# bh_netlan_0_alph.net
KiCad netlist of a schematic drawn in Altium Designer
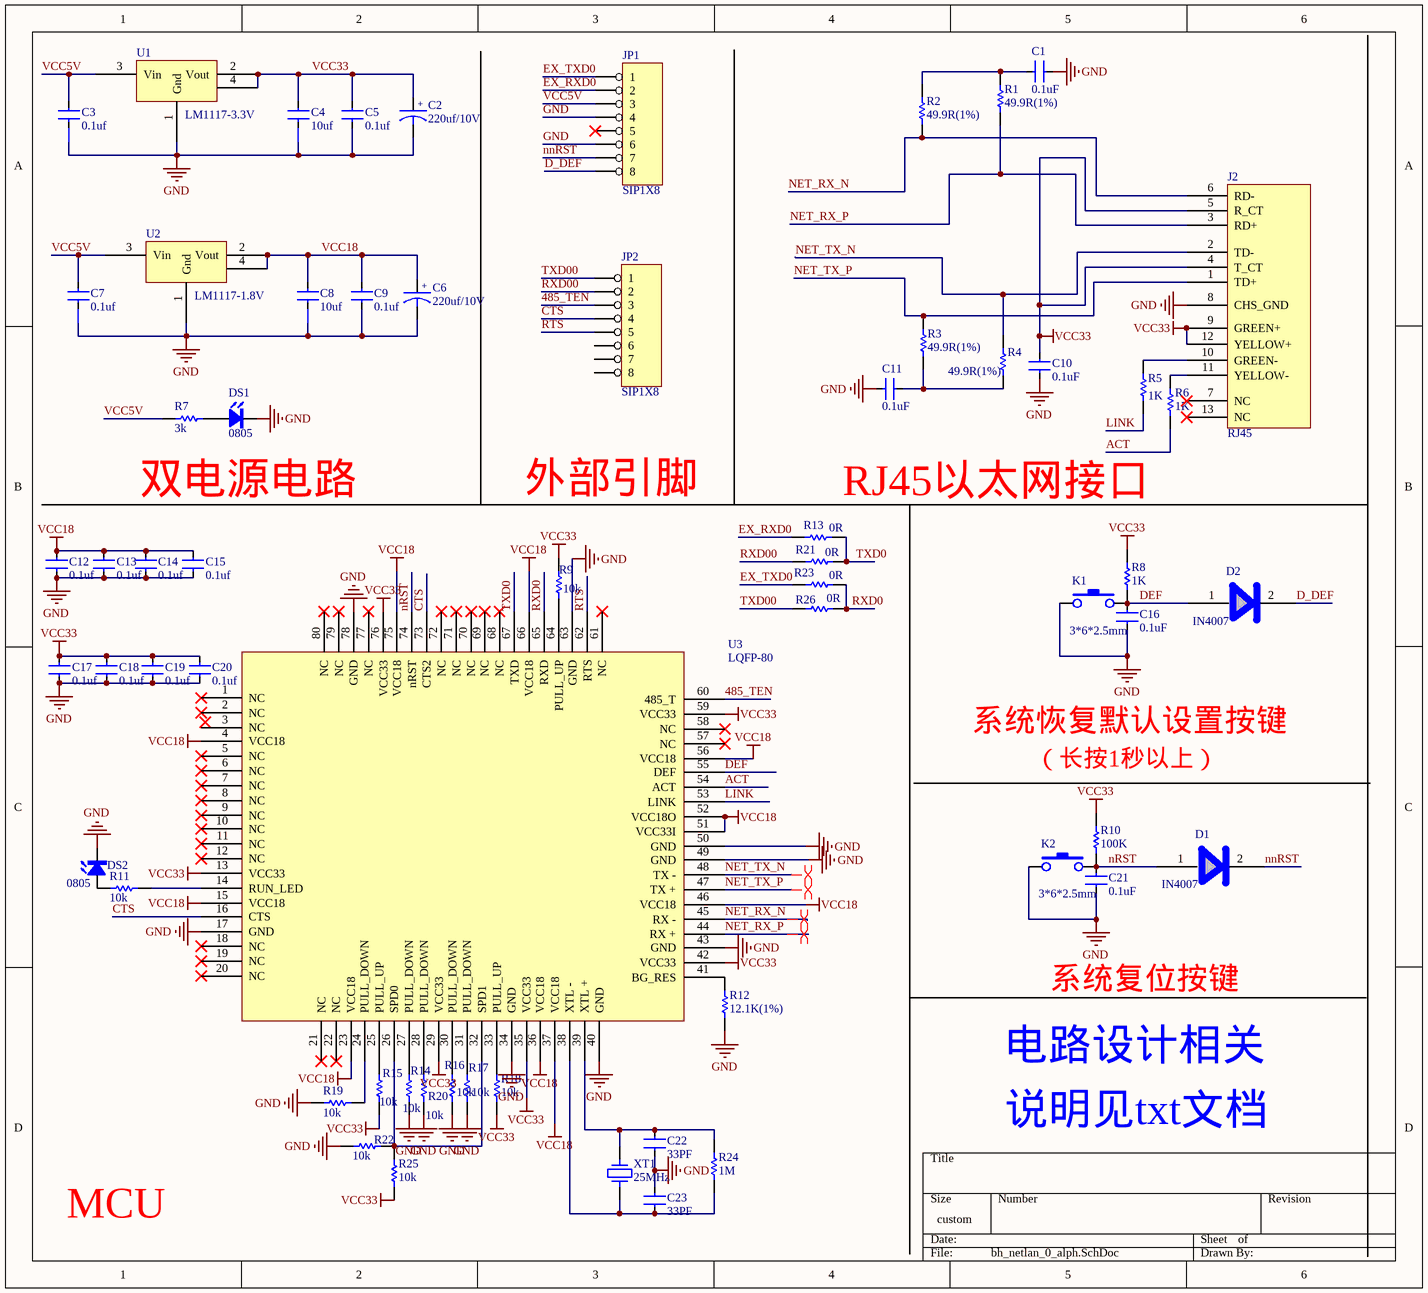
[diagram p0: bh_netlan_0_alph.SchDoc]

(export (version "E")
  (design (tool "Eeschema 10.0.6"))
  (components
    (comp (ref "C1")
      (value "0.1uF")
      (footprint "C0805")
      (description "SMD-CAP")
      (fields (field (name "Comment") "CAP-SMD"))
      (libsource (lib "5D_DEVICE") (part "CAP-SMD"))
    )
    (comp (ref "C2")
      (value "220uf/10V")
      (footprint "C6032")
      (description "钽电容")
      (libsource (lib "5D_DEVICE") (part "CAP-T"))
    )
    (comp (ref "C3")
      (value "0.1uf")
      (footprint "C0805")
      (description "SMD-CAP")
      (libsource (lib "5D_USED_DEVICE") (part "CAP-SMD"))
    )
    (comp (ref "C4")
      (value "10uf")
      (footprint "C0805")
      (description "SMD-CAP")
      (libsource (lib "5D_USED_DEVICE") (part "CAP-SMD"))
    )
    (comp (ref "C5")
      (value "0.1uf")
      (footprint "C0805")
      (description "SMD-CAP")
      (libsource (lib "5D_USED_DEVICE") (part "CAP-SMD"))
    )
    (comp (ref "C6")
      (value "220uf/10V")
      (footprint "C6032")
      (description "钽电容")
      (libsource (lib "5D_DEVICE") (part "CAP-T"))
    )
    (comp (ref "C7")
      (value "0.1uf")
      (footprint "C0805")
      (description "SMD-CAP")
      (libsource (lib "5D_USED_DEVICE") (part "CAP-SMD"))
    )
    (comp (ref "C8")
      (value "10uf")
      (footprint "C0805")
      (description "SMD-CAP")
      (libsource (lib "5D_USED_DEVICE") (part "CAP-SMD"))
    )
    (comp (ref "C9")
      (value "0.1uf")
      (footprint "C0805")
      (description "SMD-CAP")
      (libsource (lib "5D_USED_DEVICE") (part "CAP-SMD"))
    )
    (comp (ref "C10")
      (value "0.1uF")
      (footprint "C0805")
      (description "SMD-CAP")
      (fields (field (name "Comment") "CAP-SMD"))
      (libsource (lib "5D_DEVICE") (part "CAP-SMD"))
    )
    (comp (ref "C11")
      (value "0.1uF")
      (footprint "C0805")
      (description "SMD-CAP")
      (fields (field (name "Comment") "CAP-SMD"))
      (libsource (lib "5D_DEVICE") (part "CAP-SMD"))
    )
    (comp (ref "C12")
      (value "0.1uf")
      (footprint "C0603A")
      (description "SMD-CAP")
      (libsource (lib "5D_USED_DEVICE") (part "CAP-SMD"))
    )
    (comp (ref "C13")
      (value "0.1uf")
      (footprint "C0603A")
      (description "SMD-CAP")
      (libsource (lib "5D_USED_DEVICE") (part "CAP-SMD"))
    )
    (comp (ref "C14")
      (value "0.1uf")
      (footprint "C0603A")
      (description "SMD-CAP")
      (libsource (lib "5D_USED_DEVICE") (part "CAP-SMD"))
    )
    (comp (ref "C15")
      (value "0.1uf")
      (footprint "C0603A")
      (description "SMD-CAP")
      (libsource (lib "5D_USED_DEVICE") (part "CAP-SMD"))
    )
    (comp (ref "C16")
      (value "0.1uF")
      (footprint "C0805")
      (description "SMD-CAP")
      (fields (field (name "Comment") "CAP-SMD"))
      (libsource (lib "5D_DEVICE") (part "CAP-SMD"))
    )
    (comp (ref "C17")
      (value "0.1uf")
      (footprint "C0603A")
      (description "SMD-CAP")
      (libsource (lib "5D_USED_DEVICE") (part "CAP-SMD"))
    )
    (comp (ref "C18")
      (value "0.1uf")
      (footprint "C0603A")
      (description "SMD-CAP")
      (libsource (lib "5D_USED_DEVICE") (part "CAP-SMD"))
    )
    (comp (ref "C19")
      (value "0.1uf")
      (footprint "C0603A")
      (description "SMD-CAP")
      (libsource (lib "5D_USED_DEVICE") (part "CAP-SMD"))
    )
    (comp (ref "C20")
      (value "0.1uf")
      (footprint "C0603A")
      (description "SMD-CAP")
      (libsource (lib "5D_USED_DEVICE") (part "CAP-SMD"))
    )
    (comp (ref "C21")
      (value "0.1uF")
      (footprint "C0805")
      (description "SMD-CAP")
      (fields (field (name "Comment") "CAP-SMD"))
      (libsource (lib "5D_DEVICE") (part "CAP-SMD"))
    )
    (comp (ref "C22")
      (value "33PF")
      (footprint "C0603A")
      (description "SMD-CAP")
      (fields (field (name "Comment") "CAP-SMD"))
      (libsource (lib "5D_DEVICE") (part "CAP-SMD"))
    )
    (comp (ref "C23")
      (value "33PF")
      (footprint "C0603A")
      (description "SMD-CAP")
      (fields (field (name "Comment") "CAP-SMD"))
      (libsource (lib "5D_DEVICE") (part "CAP-SMD"))
    )
    (comp (ref "D1") (value "IN4007") (footprint "DO-214(SMA)") (libsource (lib "IN4007") (part "IN4007")))
    (comp (ref "D2") (value "IN4007") (footprint "DO-214(SMA)") (libsource (lib "IN4007") (part "IN4007")))
    (comp (ref "DS1") (value "0805") (footprint "LED(0805)") (libsource (lib "5D_DEVICE") (part "LED")))
    (comp (ref "DS2") (value "0805") (footprint "LED(0805)") (libsource (lib "") (part "LED_1")))
    (comp (ref "J2") (value "RJ45") (footprint "RJ45") (libsource (lib "RJ45") (part "RJ45")))
    (comp (ref "JP1")
      (value "SIP1X8")
      (footprint "SIP1x8x2.54")
      (description "8 Pin Header")
      (libsource (lib "5D_CONNECTOR") (part "SIP1X8"))
    )
    (comp (ref "JP2")
      (value "SIP1X8")
      (footprint "SIP1x8x2.54")
      (description "8 Pin Header")
      (libsource (lib "5D_CONNECTOR") (part "SIP1X8"))
    )
    (comp (ref "K1") (value "3*6*2.5mm") (footprint "key_2pin") (libsource (lib "5D_DEVICE") (part "KEY")))
    (comp (ref "K2") (value "3*6*2.5mm") (footprint "key_2pin") (libsource (lib "5D_DEVICE") (part "KEY")))
    (comp (ref "R1")
      (value "49.9R(1%)")
      (footprint "R0603")
      (description "Resistor")
      (fields (field (name "Comment") "R0603A"))
      (libsource (lib "5D_DEVICE") (part "RES"))
    )
    (comp (ref "R2")
      (value "49.9R(1%)")
      (footprint "R0603")
      (description "Resistor")
      (fields (field (name "Comment") "R0603A"))
      (libsource (lib "5D_DEVICE") (part "RES"))
    )
    (comp (ref "R3")
      (value "49.9R(1%)")
      (footprint "R0603")
      (description "Resistor")
      (fields (field (name "Comment") "R0603A"))
      (libsource (lib "5D_DEVICE") (part "RES"))
    )
    (comp (ref "R4")
      (value "49.9R(1%)")
      (footprint "R0603")
      (description "Resistor")
      (fields (field (name "Comment") "R0603A"))
      (libsource (lib "5D_DEVICE") (part "RES"))
    )
    (comp (ref "R5")
      (value "1K")
      (footprint "R0603")
      (description "Resistor")
      (fields (field (name "Comment") "R0603A"))
      (libsource (lib "5D_DEVICE") (part "RES"))
    )
    (comp (ref "R6")
      (value "1K")
      (footprint "R0603")
      (description "Resistor")
      (fields (field (name "Comment") "R0603A"))
      (libsource (lib "5D_DEVICE") (part "RES"))
    )
    (comp (ref "R7")
      (value "3k")
      (footprint "R0603")
      (description "Resistor")
      (fields (field (name "Comment") "R0603A"))
      (libsource (lib "5D_DEVICE") (part "RES"))
    )
    (comp (ref "R8")
      (value "1K")
      (footprint "R0603")
      (description "Resistor")
      (fields (field (name "Comment") "R0603A"))
      (libsource (lib "5D_DEVICE") (part "RES"))
    )
    (comp (ref "R9")
      (value "10k")
      (footprint "R0603")
      (description "Resistor")
      (fields (field (name "Comment") "R0603A"))
      (libsource (lib "5D_DEVICE") (part "RES"))
    )
    (comp (ref "R10")
      (value "100K")
      (footprint "R0603")
      (description "Resistor")
      (fields (field (name "Comment") "R0603A"))
      (libsource (lib "5D_DEVICE") (part "RES"))
    )
    (comp (ref "R11")
      (value "10k")
      (footprint "R0603")
      (description "Resistor")
      (fields (field (name "Comment") "R0603A"))
      (libsource (lib "5D_DEVICE") (part "RES"))
    )
    (comp (ref "R12")
      (value "12.1K(1%)")
      (footprint "R0603")
      (description "Resistor")
      (fields (field (name "Comment") "R0603A"))
      (libsource (lib "5D_DEVICE") (part "RES"))
    )
    (comp (ref "R13")
      (value "0R")
      (footprint "R0603")
      (description "Resistor")
      (fields (field (name "Comment") "R0603A"))
      (libsource (lib "5D_DEVICE") (part "RES"))
    )
    (comp (ref "R14")
      (value "10k")
      (footprint "R0603")
      (description "Resistor")
      (fields (field (name "Comment") "R0603A"))
      (libsource (lib "5D_DEVICE") (part "RES"))
    )
    (comp (ref "R15")
      (value "10k")
      (footprint "R0603")
      (description "Resistor")
      (fields (field (name "Comment") "R0603A"))
      (libsource (lib "5D_DEVICE") (part "RES"))
    )
    (comp (ref "R16")
      (value "10k")
      (footprint "R0603")
      (description "Resistor")
      (fields (field (name "Comment") "R0603A"))
      (libsource (lib "5D_DEVICE") (part "RES"))
    )
    (comp (ref "R17")
      (value "10k")
      (footprint "R0603")
      (description "Resistor")
      (fields (field (name "Comment") "R0603A"))
      (libsource (lib "5D_DEVICE") (part "RES"))
    )
    (comp (ref "R18")
      (value "10k")
      (footprint "R0603")
      (description "Resistor")
      (fields (field (name "Comment") "R0603A"))
      (libsource (lib "5D_DEVICE") (part "RES"))
    )
    (comp (ref "R19")
      (value "10k")
      (footprint "R0603")
      (description "Resistor")
      (fields (field (name "Comment") "R0603A"))
      (libsource (lib "5D_DEVICE") (part "RES"))
    )
    (comp (ref "R20")
      (value "10k")
      (footprint "R0603")
      (description "Resistor")
      (fields (field (name "Comment") "R0603A"))
      (libsource (lib "5D_DEVICE") (part "RES"))
    )
    (comp (ref "R21")
      (value "0R")
      (footprint "R0603")
      (description "Resistor")
      (fields (field (name "Comment") "R0603A"))
      (libsource (lib "5D_DEVICE") (part "RES"))
    )
    (comp (ref "R22")
      (value "10k")
      (footprint "R0603")
      (description "Resistor")
      (fields (field (name "Comment") "R0603A"))
      (libsource (lib "5D_DEVICE") (part "RES"))
    )
    (comp (ref "R23")
      (value "0R")
      (footprint "R0603")
      (description "Resistor")
      (fields (field (name "Comment") "R0603A"))
      (libsource (lib "5D_DEVICE") (part "RES"))
    )
    (comp (ref "R24")
      (value "1M")
      (footprint "R0603")
      (description "Resistor")
      (fields (field (name "Comment") "R0603A"))
      (libsource (lib "5D_DEVICE") (part "RES"))
    )
    (comp (ref "R25")
      (value "10k")
      (footprint "R0603")
      (description "Resistor")
      (fields (field (name "Comment") "R0603A"))
      (libsource (lib "5D_DEVICE") (part "RES"))
    )
    (comp (ref "R26")
      (value "0R")
      (footprint "R0603")
      (description "Resistor")
      (fields (field (name "Comment") "R0603A"))
      (libsource (lib "5D_DEVICE") (part "RES"))
    )
    (comp (ref "U1")
      (value "LM1117-3.3V")
      (footprint "SOT-223")
      (description "ASM1117-2.5V")
      (libsource (lib "5D_USED_DEVICE") (part "ASM1117-2.5V"))
    )
    (comp (ref "U2")
      (value "LM1117-1.8V")
      (footprint "SOT-223")
      (description "ASM1117-2.5V")
      (libsource (lib "5D_USED_DEVICE") (part "ASM1117-2.5V"))
    )
    (comp (ref "U3") (value "LQFP-80") (footprint "LQFP-80") (libsource (lib "ZLAN1003") (part "ZLAN1003")))
    (comp (ref "XT1")
      (value "25MHz")
      (footprint "XTAL/HC-49S")
      (description "晶振")
      (libsource (lib "5D_DEVICE") (part "XT"))
    )
  )
  (nets
    (net (code "1") (name "/485_TEN") (class "Default")
      (node (ref "JP2") (pin "3") (pinfunction "3_3") (pintype "passive"))
      (node (ref "U3") (pin "60") (pinfunction "485_T_60") (pintype "passive"))
    )
    (net (code "2") (name "/ACT") (class "Default")
      (node (ref "R6") (pin "2") (pinfunction "2_2") (pintype "passive"))
      (node (ref "U3") (pin "54") (pinfunction "ACT_54") (pintype "passive"))
    )
    (net (code "3") (name "/CTS") (class "Default")
      (node (ref "JP2") (pin "4") (pinfunction "4_4") (pintype "passive"))
      (node (ref "U3") (pin "16") (pinfunction "CTS_16") (pintype "passive"))
      (node (ref "U3") (pin "73") (pinfunction "CTS2_73") (pintype "passive"))
    )
    (net (code "4") (name "/DEF") (class "Default")
      (node (ref "C16") (pin "2") (pinfunction "2_2") (pintype "passive"))
      (node (ref "D2") (pin "1") (pinfunction "1_1") (pintype "passive"))
      (node (ref "K1") (pin "2") (pinfunction "2_2") (pintype "passive"))
      (node (ref "R8") (pin "2") (pinfunction "2_2") (pintype "passive"))
      (node (ref "U3") (pin "55") (pinfunction "DEF_55") (pintype "passive"))
    )
    (net (code "5") (name "/D_DEF") (class "Default")
      (node (ref "D2") (pin "2") (pinfunction "2_2") (pintype "passive"))
      (node (ref "JP1") (pin "8") (pinfunction "8_8") (pintype "passive"))
    )
    (net (code "6") (name "/EX_RXD0") (class "Default")
      (node (ref "JP1") (pin "2") (pinfunction "2_2") (pintype "passive"))
      (node (ref "R13") (pin "2") (pinfunction "2_2") (pintype "passive"))
    )
    (net (code "7") (name "/EX_TXD0") (class "Default")
      (node (ref "JP1") (pin "1") (pinfunction "1_1") (pintype "passive"))
      (node (ref "R23") (pin "2") (pinfunction "2_2") (pintype "passive"))
    )
    (net (code "8") (name "/LINK") (class "Default")
      (node (ref "R5") (pin "2") (pinfunction "2_2") (pintype "passive"))
      (node (ref "U3") (pin "53") (pinfunction "LINK_53") (pintype "passive"))
    )
    (net (code "9") (name "/NET_RX_N") (class "Default")
      (node (ref "J2") (pin "6") (pinfunction "RD-_6") (pintype "passive"))
      (node (ref "R2") (pin "2") (pinfunction "2_2") (pintype "passive"))
      (node (ref "U3") (pin "45") (pinfunction "RX_-_45") (pintype "passive"))
    )
    (net (code "10") (name "/NET_RX_P") (class "Default")
      (node (ref "J2") (pin "3") (pinfunction "RD+_3") (pintype "passive"))
      (node (ref "R1") (pin "2") (pinfunction "2_2") (pintype "passive"))
      (node (ref "U3") (pin "44") (pinfunction "RX_+_44") (pintype "passive"))
    )
    (net (code "11") (name "/NET_TX_N") (class "Default")
      (node (ref "J2") (pin "2") (pinfunction "TD-_2") (pintype "passive"))
      (node (ref "R4") (pin "1") (pinfunction "1_1") (pintype "passive"))
      (node (ref "U3") (pin "48") (pinfunction "TX_-_48") (pintype "passive"))
    )
    (net (code "12") (name "/NET_TX_P") (class "Default")
      (node (ref "J2") (pin "1") (pinfunction "TD+_1") (pintype "passive"))
      (node (ref "R3") (pin "1") (pinfunction "1_1") (pintype "passive"))
      (node (ref "U3") (pin "47") (pinfunction "TX_+_47") (pintype "passive"))
    )
    (net (code "13") (name "/RTS") (class "Default")
      (node (ref "JP2") (pin "5") (pinfunction "5_5") (pintype "passive"))
      (node (ref "U3") (pin "62") (pinfunction "RTS_62") (pintype "passive"))
    )
    (net (code "14") (name "/RXD0") (class "Default")
      (node (ref "R23") (pin "1") (pinfunction "1_1") (pintype "passive"))
      (node (ref "R26") (pin "1") (pinfunction "1_1") (pintype "passive"))
      (node (ref "U3") (pin "65") (pinfunction "RXD_65") (pintype "passive"))
    )
    (net (code "15") (name "/RXD00") (class "Default")
      (node (ref "JP2") (pin "2") (pinfunction "2_2") (pintype "passive"))
      (node (ref "R21") (pin "2") (pinfunction "2_2") (pintype "passive"))
    )
    (net (code "16") (name "/TXD0") (class "Default")
      (node (ref "R13") (pin "1") (pinfunction "1_1") (pintype "passive"))
      (node (ref "R21") (pin "1") (pinfunction "1_1") (pintype "passive"))
      (node (ref "U3") (pin "67") (pinfunction "TXD_67") (pintype "passive"))
    )
    (net (code "17") (name "/TXD00") (class "Default")
      (node (ref "JP2") (pin "1") (pinfunction "1_1") (pintype "passive"))
      (node (ref "R26") (pin "2") (pinfunction "2_2") (pintype "passive"))
    )
    (net (code "18") (name "/VCC5V") (class "Default")
      (node (ref "C3") (pin "1") (pinfunction "1_1") (pintype "passive"))
      (node (ref "C7") (pin "1") (pinfunction "1_1") (pintype "passive"))
      (node (ref "JP1") (pin "3") (pinfunction "3_3") (pintype "passive"))
      (node (ref "R7") (pin "2") (pinfunction "2_2") (pintype "passive"))
      (node (ref "U1") (pin "3") (pinfunction "Vin_3") (pintype "passive"))
      (node (ref "U2") (pin "3") (pinfunction "Vin_3") (pintype "passive"))
    )
    (net (code "19") (name "/nRST") (class "Default")
      (node (ref "C21") (pin "2") (pinfunction "2_2") (pintype "passive"))
      (node (ref "D1") (pin "1") (pinfunction "1_1") (pintype "passive"))
      (node (ref "K2") (pin "2") (pinfunction "2_2") (pintype "passive"))
      (node (ref "R10") (pin "2") (pinfunction "2_2") (pintype "passive"))
      (node (ref "U3") (pin "74") (pinfunction "nRST_74") (pintype "passive"))
    )
    (net (code "20") (name "/nnRST") (class "Default")
      (node (ref "D1") (pin "2") (pinfunction "2_2") (pintype "passive"))
      (node (ref "JP1") (pin "7") (pinfunction "7_7") (pintype "passive"))
    )
    (net (code "21") (name "GND") (class "Default")
      (node (ref "C1") (pin "1") (pinfunction "1_1") (pintype "passive"))
      (node (ref "C10") (pin "1") (pinfunction "1_1") (pintype "passive"))
      (node (ref "C11") (pin "2") (pinfunction "2_2") (pintype "passive"))
      (node (ref "C12") (pin "2") (pinfunction "2_2") (pintype "passive"))
      (node (ref "C13") (pin "2") (pinfunction "2_2") (pintype "passive"))
      (node (ref "C14") (pin "2") (pinfunction "2_2") (pintype "passive"))
      (node (ref "C15") (pin "2") (pinfunction "2_2") (pintype "passive"))
      (node (ref "C16") (pin "1") (pinfunction "1_1") (pintype "passive"))
      (node (ref "C17") (pin "2") (pinfunction "2_2") (pintype "passive"))
      (node (ref "C18") (pin "2") (pinfunction "2_2") (pintype "passive"))
      (node (ref "C19") (pin "2") (pinfunction "2_2") (pintype "passive"))
      (node (ref "C2") (pin "2") (pinfunction "2_2") (pintype "passive"))
      (node (ref "C20") (pin "2") (pinfunction "2_2") (pintype "passive"))
      (node (ref "C21") (pin "1") (pinfunction "1_1") (pintype "passive"))
      (node (ref "C22") (pin "1") (pinfunction "1_1") (pintype "passive"))
      (node (ref "C23") (pin "2") (pinfunction "2_2") (pintype "passive"))
      (node (ref "C3") (pin "2") (pinfunction "2_2") (pintype "passive"))
      (node (ref "C4") (pin "2") (pinfunction "2_2") (pintype "passive"))
      (node (ref "C5") (pin "2") (pinfunction "2_2") (pintype "passive"))
      (node (ref "C6") (pin "2") (pinfunction "2_2") (pintype "passive"))
      (node (ref "C7") (pin "2") (pinfunction "2_2") (pintype "passive"))
      (node (ref "C8") (pin "2") (pinfunction "2_2") (pintype "passive"))
      (node (ref "C9") (pin "2") (pinfunction "2_2") (pintype "passive"))
      (node (ref "DS1") (pin "K") (pinfunction "2_K") (pintype "passive"))
      (node (ref "DS2") (pin "K") (pinfunction "2_K") (pintype "passive"))
      (node (ref "J2") (pin "8") (pinfunction "CHS_GND_8") (pintype "passive"))
      (node (ref "JP1") (pin "4") (pinfunction "4_4") (pintype "passive"))
      (node (ref "JP1") (pin "6") (pinfunction "6_6") (pintype "passive"))
      (node (ref "K1") (pin "1") (pinfunction "1_1") (pintype "passive"))
      (node (ref "K2") (pin "1") (pinfunction "1_1") (pintype "passive"))
      (node (ref "R12") (pin "2") (pinfunction "2_2") (pintype "passive"))
      (node (ref "R14") (pin "1") (pinfunction "1_1") (pintype "passive"))
      (node (ref "R16") (pin "1") (pinfunction "1_1") (pintype "passive"))
      (node (ref "R17") (pin "1") (pinfunction "1_1") (pintype "passive"))
      (node (ref "R19") (pin "1") (pinfunction "1_1") (pintype "passive"))
      (node (ref "R20") (pin "1") (pinfunction "1_1") (pintype "passive"))
      (node (ref "R22") (pin "2") (pinfunction "2_2") (pintype "passive"))
      (node (ref "U1") (pin "1") (pinfunction "Gnd_1") (pintype "passive"))
      (node (ref "U2") (pin "1") (pinfunction "Gnd_1") (pintype "passive"))
      (node (ref "U3") (pin "17") (pinfunction "GND_17") (pintype "passive"))
      (node (ref "U3") (pin "34") (pinfunction "GND_34") (pintype "passive"))
      (node (ref "U3") (pin "40") (pinfunction "GND_40") (pintype "passive"))
      (node (ref "U3") (pin "43") (pinfunction "GND_43") (pintype "passive"))
      (node (ref "U3") (pin "49") (pinfunction "GND_49") (pintype "passive"))
      (node (ref "U3") (pin "50") (pinfunction "GND_50") (pintype "passive"))
      (node (ref "U3") (pin "63") (pinfunction "GND_63") (pintype "passive"))
      (node (ref "U3") (pin "78") (pinfunction "GND_78") (pintype "passive"))
    )
    (net (code "22") (name "Net-(C1-Pad2)") (class "Default")
      (node (ref "C1") (pin "2") (pinfunction "2_2") (pintype "passive"))
      (node (ref "R1") (pin "1") (pinfunction "1_1") (pintype "passive"))
      (node (ref "R2") (pin "1") (pinfunction "1_1") (pintype "passive"))
    )
    (net (code "23") (name "Net-(C11-Pad1)") (class "Default")
      (node (ref "C11") (pin "1") (pinfunction "1_1") (pintype "passive"))
      (node (ref "R3") (pin "2") (pinfunction "2_2") (pintype "passive"))
      (node (ref "R4") (pin "2") (pinfunction "2_2") (pintype "passive"))
    )
    (net (code "24") (name "Net-(DS1-1)") (class "Default")
      (node (ref "DS1") (pin "A") (pinfunction "1_A") (pintype "passive"))
      (node (ref "R7") (pin "1") (pinfunction "1_1") (pintype "passive"))
    )
    (net (code "25") (name "Net-(DS2-1)") (class "Default")
      (node (ref "DS2") (pin "A") (pinfunction "1_A") (pintype "passive"))
      (node (ref "R11") (pin "2") (pinfunction "2_2") (pintype "passive"))
    )
    (net (code "26") (name "Net-(J2-GREEN-)") (class "Default")
      (node (ref "J2") (pin "10") (pinfunction "GREEN-_10") (pintype "passive"))
      (node (ref "R5") (pin "1") (pinfunction "1_1") (pintype "passive"))
    )
    (net (code "27") (name "Net-(J2-YELLOW-)") (class "Default")
      (node (ref "J2") (pin "11") (pinfunction "YELLOW-_11") (pintype "passive"))
      (node (ref "R6") (pin "1") (pinfunction "1_1") (pintype "passive"))
    )
    (net (code "28") (name "Net-(R9-Pad1)") (class "Default")
      (node (ref "R9") (pin "1") (pinfunction "1_1") (pintype "passive"))
      (node (ref "U3") (pin "64") (pinfunction "PULL_UP_64") (pintype "passive"))
    )
    (net (code "29") (name "Net-(R14-Pad2)") (class "Default")
      (node (ref "R14") (pin "2") (pinfunction "2_2") (pintype "passive"))
      (node (ref "U3") (pin "27") (pinfunction "PULL_DOWN_27") (pintype "passive"))
    )
    (net (code "30") (name "Net-(R15-Pad2)") (class "Default")
      (node (ref "R15") (pin "2") (pinfunction "2_2") (pintype "passive"))
      (node (ref "U3") (pin "25") (pinfunction "PULL_UP_25") (pintype "passive"))
    )
    (net (code "31") (name "Net-(R16-Pad2)") (class "Default")
      (node (ref "R16") (pin "2") (pinfunction "2_2") (pintype "passive"))
      (node (ref "U3") (pin "30") (pinfunction "PULL_DOWN_30") (pintype "passive"))
    )
    (net (code "32") (name "Net-(R17-Pad2)") (class "Default")
      (node (ref "R17") (pin "2") (pinfunction "2_2") (pintype "passive"))
      (node (ref "U3") (pin "31") (pinfunction "PULL_DOWN_31") (pintype "passive"))
    )
    (net (code "33") (name "Net-(R18-Pad2)") (class "Default")
      (node (ref "R18") (pin "2") (pinfunction "2_2") (pintype "passive"))
      (node (ref "U3") (pin "33") (pinfunction "PULL_UP_33") (pintype "passive"))
    )
    (net (code "34") (name "Net-(R19-Pad2)") (class "Default")
      (node (ref "R19") (pin "2") (pinfunction "2_2") (pintype "passive"))
      (node (ref "U3") (pin "24") (pinfunction "PULL_DOWN_24") (pintype "passive"))
    )
    (net (code "35") (name "Net-(R20-Pad2)") (class "Default")
      (node (ref "R20") (pin "2") (pinfunction "2_2") (pintype "passive"))
      (node (ref "U3") (pin "28") (pinfunction "PULL_DOWN_28") (pintype "passive"))
    )
    (net (code "36") (name "Net-(U3-BG_RES)") (class "Default")
      (node (ref "R12") (pin "1") (pinfunction "1_1") (pintype "passive"))
      (node (ref "U3") (pin "41") (pinfunction "BG_RES_41") (pintype "passive"))
    )
    (net (code "37") (name "Net-(U3-RUN_LED)") (class "Default")
      (node (ref "R11") (pin "1") (pinfunction "1_1") (pintype "passive"))
      (node (ref "U3") (pin "14") (pinfunction "RUN_LED_14") (pintype "passive"))
    )
    (net (code "38") (name "Net-(U3-SPD0)") (class "Default")
      (node (ref "R22") (pin "1") (pinfunction "1_1") (pintype "passive"))
      (node (ref "R25") (pin "2") (pinfunction "2_2") (pintype "passive"))
      (node (ref "U3") (pin "26") (pinfunction "SPD0_26") (pintype "passive"))
      (node (ref "U3") (pin "32") (pinfunction "SPD1_32") (pintype "passive"))
    )
    (net (code "39") (name "Net-(U3-XTL_+)") (class "Default")
      (node (ref "C22") (pin "2") (pinfunction "2_2") (pintype "passive"))
      (node (ref "R24") (pin "1") (pinfunction "1_1") (pintype "passive"))
      (node (ref "U3") (pin "39") (pinfunction "XTL_+_39") (pintype "passive"))
      (node (ref "XT1") (pin "2") (pinfunction "2_2") (pintype "passive"))
    )
    (net (code "40") (name "Net-(U3-XTL_-)") (class "Default")
      (node (ref "C23") (pin "1") (pinfunction "1_1") (pintype "passive"))
      (node (ref "R24") (pin "2") (pinfunction "2_2") (pintype "passive"))
      (node (ref "U3") (pin "38") (pinfunction "XTL_-_38") (pintype "passive"))
      (node (ref "XT1") (pin "1") (pinfunction "1_1") (pintype "passive"))
    )
    (net (code "41") (name "VCC18") (class "Default")
      (node (ref "C12") (pin "1") (pinfunction "1_1") (pintype "passive"))
      (node (ref "C13") (pin "1") (pinfunction "1_1") (pintype "passive"))
      (node (ref "C14") (pin "1") (pinfunction "1_1") (pintype "passive"))
      (node (ref "C15") (pin "1") (pinfunction "1_1") (pintype "passive"))
      (node (ref "C6") (pin "1") (pinfunction "1_1") (pintype "passive"))
      (node (ref "C8") (pin "1") (pinfunction "1_1") (pintype "passive"))
      (node (ref "C9") (pin "1") (pinfunction "1_1") (pintype "passive"))
      (node (ref "U2") (pin "2") (pinfunction "Vout_2") (pintype "passive"))
      (node (ref "U2") (pin "4") (pinfunction "4_4") (pintype "passive"))
      (node (ref "U3") (pin "15") (pinfunction "VCC18_15") (pintype "passive"))
      (node (ref "U3") (pin "23") (pinfunction "VCC18_23") (pintype "passive"))
      (node (ref "U3") (pin "36") (pinfunction "VCC18_36") (pintype "passive"))
      (node (ref "U3") (pin "37") (pinfunction "VCC18_37") (pintype "passive"))
      (node (ref "U3") (pin "4") (pinfunction "VCC18_4") (pintype "passive"))
      (node (ref "U3") (pin "46") (pinfunction "VCC18_46") (pintype "passive"))
      (node (ref "U3") (pin "51") (pinfunction "VCC33I_51") (pintype "passive"))
      (node (ref "U3") (pin "52") (pinfunction "VCC18O_52") (pintype "passive"))
      (node (ref "U3") (pin "56") (pinfunction "VCC18_56") (pintype "passive"))
      (node (ref "U3") (pin "66") (pinfunction "VCC18_66") (pintype "passive"))
      (node (ref "U3") (pin "75") (pinfunction "VCC18_75") (pintype "passive"))
    )
    (net (code "42") (name "VCC33") (class "Default")
      (node (ref "C10") (pin "2") (pinfunction "2_2") (pintype "passive"))
      (node (ref "C17") (pin "1") (pinfunction "1_1") (pintype "passive"))
      (node (ref "C18") (pin "1") (pinfunction "1_1") (pintype "passive"))
      (node (ref "C19") (pin "1") (pinfunction "1_1") (pintype "passive"))
      (node (ref "C2") (pin "1") (pinfunction "1_1") (pintype "passive"))
      (node (ref "C20") (pin "1") (pinfunction "1_1") (pintype "passive"))
      (node (ref "C4") (pin "1") (pinfunction "1_1") (pintype "passive"))
      (node (ref "C5") (pin "1") (pinfunction "1_1") (pintype "passive"))
      (node (ref "J2") (pin "12") (pinfunction "YELLOW+_12") (pintype "passive"))
      (node (ref "J2") (pin "4") (pinfunction "T_CT_4") (pintype "passive"))
      (node (ref "J2") (pin "5") (pinfunction "R_CT_5") (pintype "passive"))
      (node (ref "J2") (pin "9") (pinfunction "GREEN+_9") (pintype "passive"))
      (node (ref "R10") (pin "1") (pinfunction "1_1") (pintype "passive"))
      (node (ref "R15") (pin "1") (pinfunction "1_1") (pintype "passive"))
      (node (ref "R18") (pin "1") (pinfunction "1_1") (pintype "passive"))
      (node (ref "R25") (pin "1") (pinfunction "1_1") (pintype "passive"))
      (node (ref "R8") (pin "1") (pinfunction "1_1") (pintype "passive"))
      (node (ref "R9") (pin "2") (pinfunction "2_2") (pintype "passive"))
      (node (ref "U1") (pin "2") (pinfunction "Vout_2") (pintype "passive"))
      (node (ref "U1") (pin "4") (pinfunction "4_4") (pintype "passive"))
      (node (ref "U3") (pin "13") (pinfunction "VCC33_13") (pintype "passive"))
      (node (ref "U3") (pin "29") (pinfunction "VCC33_29") (pintype "passive"))
      (node (ref "U3") (pin "35") (pinfunction "VCC33_35") (pintype "passive"))
      (node (ref "U3") (pin "42") (pinfunction "VCC33_42") (pintype "passive"))
      (node (ref "U3") (pin "59") (pinfunction "VCC33_59") (pintype "passive"))
      (node (ref "U3") (pin "76") (pinfunction "VCC33_76") (pintype "passive"))
    )
    (net (code "43") (name "unconnected-(J2-NC-Pad7)") (class "Default")
      (node (ref "J2") (pin "7") (pinfunction "NC_7") (pintype "passive+no_connect"))
    )
    (net (code "44") (name "unconnected-(J2-NC-Pad13)") (class "Default")
      (node (ref "J2") (pin "13") (pinfunction "NC_13") (pintype "passive+no_connect"))
    )
    (net (code "45") (name "unconnected-(JP1-Pad5)") (class "Default")
      (node (ref "JP1") (pin "5") (pinfunction "5_5") (pintype "passive+no_connect"))
    )
    (net (code "46") (name "unconnected-(JP2-Pad6)") (class "Default")
      (node (ref "JP2") (pin "6") (pinfunction "6_6") (pintype "passive"))
    )
    (net (code "47") (name "unconnected-(JP2-Pad7)") (class "Default")
      (node (ref "JP2") (pin "7") (pinfunction "7_7") (pintype "passive"))
    )
    (net (code "48") (name "unconnected-(JP2-Pad8)") (class "Default")
      (node (ref "JP2") (pin "8") (pinfunction "8_8") (pintype "passive"))
    )
    (net (code "49") (name "unconnected-(U3-NC-Pad1)") (class "Default")
      (node (ref "U3") (pin "1") (pinfunction "NC_1") (pintype "passive+no_connect"))
    )
    (net (code "50") (name "unconnected-(U3-NC-Pad2)") (class "Default")
      (node (ref "U3") (pin "2") (pinfunction "NC_2") (pintype "passive+no_connect"))
    )
    (net (code "51") (name "unconnected-(U3-NC-Pad3)") (class "Default")
      (node (ref "U3") (pin "3") (pinfunction "NC_3") (pintype "passive"))
    )
    (net (code "52") (name "unconnected-(U3-NC-Pad5)") (class "Default")
      (node (ref "U3") (pin "5") (pinfunction "NC_5") (pintype "passive+no_connect"))
    )
    (net (code "53") (name "unconnected-(U3-NC-Pad6)") (class "Default")
      (node (ref "U3") (pin "6") (pinfunction "NC_6") (pintype "passive+no_connect"))
    )
    (net (code "54") (name "unconnected-(U3-NC-Pad7)") (class "Default")
      (node (ref "U3") (pin "7") (pinfunction "NC_7") (pintype "passive+no_connect"))
    )
    (net (code "55") (name "unconnected-(U3-NC-Pad8)") (class "Default")
      (node (ref "U3") (pin "8") (pinfunction "NC_8") (pintype "passive+no_connect"))
    )
    (net (code "56") (name "unconnected-(U3-NC-Pad9)") (class "Default")
      (node (ref "U3") (pin "9") (pinfunction "NC_9") (pintype "passive+no_connect"))
    )
    (net (code "57") (name "unconnected-(U3-NC-Pad10)") (class "Default")
      (node (ref "U3") (pin "10") (pinfunction "NC_10") (pintype "passive+no_connect"))
    )
    (net (code "58") (name "unconnected-(U3-NC-Pad11)") (class "Default")
      (node (ref "U3") (pin "11") (pinfunction "NC_11") (pintype "passive+no_connect"))
    )
    (net (code "59") (name "unconnected-(U3-NC-Pad12)") (class "Default")
      (node (ref "U3") (pin "12") (pinfunction "NC_12") (pintype "passive+no_connect"))
    )
    (net (code "60") (name "unconnected-(U3-NC-Pad18)") (class "Default")
      (node (ref "U3") (pin "18") (pinfunction "NC_18") (pintype "passive+no_connect"))
    )
    (net (code "61") (name "unconnected-(U3-NC-Pad19)") (class "Default")
      (node (ref "U3") (pin "19") (pinfunction "NC_19") (pintype "passive+no_connect"))
    )
    (net (code "62") (name "unconnected-(U3-NC-Pad20)") (class "Default")
      (node (ref "U3") (pin "20") (pinfunction "NC_20") (pintype "passive+no_connect"))
    )
    (net (code "63") (name "unconnected-(U3-NC-Pad21)") (class "Default")
      (node (ref "U3") (pin "21") (pinfunction "NC_21") (pintype "passive+no_connect"))
    )
    (net (code "64") (name "unconnected-(U3-NC-Pad22)") (class "Default")
      (node (ref "U3") (pin "22") (pinfunction "NC_22") (pintype "passive+no_connect"))
    )
    (net (code "65") (name "unconnected-(U3-NC-Pad57)") (class "Default")
      (node (ref "U3") (pin "57") (pinfunction "NC_57") (pintype "passive+no_connect"))
    )
    (net (code "66") (name "unconnected-(U3-NC-Pad58)") (class "Default")
      (node (ref "U3") (pin "58") (pinfunction "NC_58") (pintype "passive+no_connect"))
    )
    (net (code "67") (name "unconnected-(U3-NC-Pad61)") (class "Default")
      (node (ref "U3") (pin "61") (pinfunction "NC_61") (pintype "passive+no_connect"))
    )
    (net (code "68") (name "unconnected-(U3-NC-Pad68)") (class "Default")
      (node (ref "U3") (pin "68") (pinfunction "NC_68") (pintype "passive+no_connect"))
    )
    (net (code "69") (name "unconnected-(U3-NC-Pad69)") (class "Default")
      (node (ref "U3") (pin "69") (pinfunction "NC_69") (pintype "passive+no_connect"))
    )
    (net (code "70") (name "unconnected-(U3-NC-Pad70)") (class "Default")
      (node (ref "U3") (pin "70") (pinfunction "NC_70") (pintype "passive+no_connect"))
    )
    (net (code "71") (name "unconnected-(U3-NC-Pad71)") (class "Default")
      (node (ref "U3") (pin "71") (pinfunction "NC_71") (pintype "passive+no_connect"))
    )
    (net (code "72") (name "unconnected-(U3-NC-Pad72)") (class "Default")
      (node (ref "U3") (pin "72") (pinfunction "NC_72") (pintype "passive+no_connect"))
    )
    (net (code "73") (name "unconnected-(U3-NC-Pad77)") (class "Default")
      (node (ref "U3") (pin "77") (pinfunction "NC_77") (pintype "passive+no_connect"))
    )
    (net (code "74") (name "unconnected-(U3-NC-Pad79)") (class "Default")
      (node (ref "U3") (pin "79") (pinfunction "NC_79") (pintype "passive+no_connect"))
    )
    (net (code "75") (name "unconnected-(U3-NC-Pad80)") (class "Default")
      (node (ref "U3") (pin "80") (pinfunction "NC_80") (pintype "passive+no_connect"))
    )
  )
)
